# io-headers.net
KiCad netlist of a schematic drawn in Altium Designer
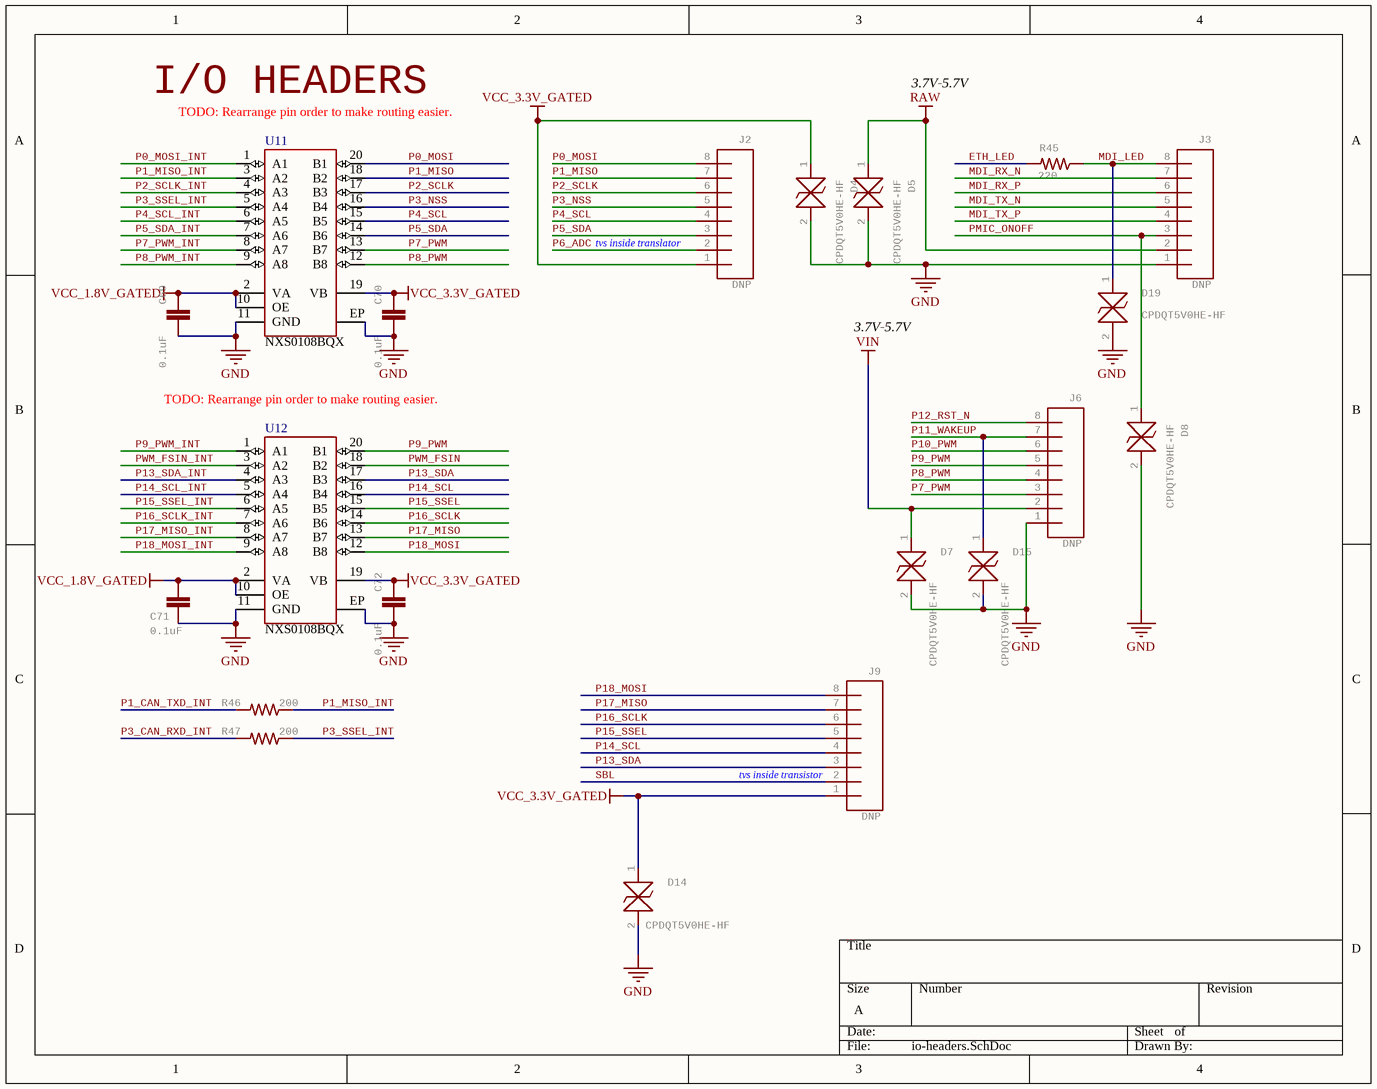
[diagram p0: io-headers.SchDoc]

(export (version "E")
  (design (tool "Eeschema 10.0.6"))
  (components
    (comp (ref "C69")
      (value "0.1uF")
      (footprint "0402-CAP")
      (description "CAPACITOR, European symbol")
      (fields (field (name "MPN") "C0402C104Z4VAC"))
      (libsource (lib "openmv-ae3") (part "C-EUC0201"))
    )
    (comp (ref "C70")
      (value "0.1uF")
      (footprint "0402-CAP")
      (description "CAPACITOR, European symbol")
      (fields (field (name "MPN") "C0402C104Z4VAC"))
      (libsource (lib "openmv-ae3") (part "C-EUC0201"))
    )
    (comp (ref "C71")
      (value "0.1uF")
      (footprint "0402-CAP")
      (description "CAPACITOR, European symbol")
      (fields (field (name "MPN") "C0402C104Z4VAC"))
      (libsource (lib "openmv-ae3") (part "C-EUC0201"))
    )
    (comp (ref "C72")
      (value "0.1uF")
      (footprint "0402-CAP")
      (description "CAPACITOR, European symbol")
      (fields (field (name "MPN") "C0402C104Z4VAC"))
      (libsource (lib "openmv-ae3") (part "C-EUC0201"))
    )
    (comp (ref "D4")
      (value "CPDQT5V0HE-HF")
      (footprint "CPDQT5V0HEHF")
      (description "ESD Suppressors / TVS Diodes DIODE ESD 5VWM 65W 0402/SOD-923F   Source:  Datasheet")
      (fields (field (name "MOUSER_PART_NUMBER") "MOUSER_PART_NUMBER"))
      (libsource (lib "openmv-ae3") (part "CPDQT5V0HE-HF"))
    )
    (comp (ref "D5")
      (value "CPDQT5V0HE-HF")
      (footprint "CPDQT5V0HEHF")
      (description "ESD Suppressors / TVS Diodes DIODE ESD 5VWM 65W 0402/SOD-923F   Source:  Datasheet")
      (fields (field (name "MOUSER_PART_NUMBER") "MOUSER_PART_NUMBER"))
      (libsource (lib "openmv-ae3") (part "CPDQT5V0HE-HF"))
    )
    (comp (ref "D7")
      (value "CPDQT5V0HE-HF")
      (footprint "CPDQT5V0HEHF")
      (description "ESD Suppressors / TVS Diodes DIODE ESD 5VWM 65W 0402/SOD-923F   Source:  Datasheet")
      (fields (field (name "MOUSER_PART_NUMBER") "MOUSER_PART_NUMBER"))
      (libsource (lib "openmv-ae3") (part "CPDQT5V0HE-HF"))
    )
    (comp (ref "D8")
      (value "CPDQT5V0HE-HF")
      (footprint "CPDQT5V0HEHF")
      (description "ESD Suppressors / TVS Diodes DIODE ESD 5VWM 65W 0402/SOD-923F   Source:  Datasheet")
      (fields (field (name "MOUSER_PART_NUMBER") "MOUSER_PART_NUMBER"))
      (libsource (lib "openmv-ae3") (part "CPDQT5V0HE-HF"))
    )
    (comp (ref "D14")
      (value "CPDQT5V0HE-HF")
      (footprint "CPDQT5V0HEHF")
      (description "ESD Suppressors / TVS Diodes DIODE ESD 5VWM 65W 0402/SOD-923F   Source:  Datasheet")
      (fields (field (name "MOUSER_PART_NUMBER") "MOUSER_PART_NUMBER"))
      (libsource (lib "openmv-ae3") (part "CPDQT5V0HE-HF"))
    )
    (comp (ref "D15")
      (value "CPDQT5V0HE-HF")
      (footprint "CPDQT5V0HEHF")
      (description "ESD Suppressors / TVS Diodes DIODE ESD 5VWM 65W 0402/SOD-923F   Source:  Datasheet")
      (fields (field (name "MOUSER_PART_NUMBER") "MOUSER_PART_NUMBER"))
      (libsource (lib "openmv-ae3") (part "CPDQT5V0HE-HF"))
    )
    (comp (ref "D19")
      (value "CPDQT5V0HE-HF")
      (footprint "CPDQT5V0HEHF")
      (description "ESD Suppressors / TVS Diodes DIODE ESD 5VWM 65W 0402/SOD-923F   Source:  Datasheet")
      (fields (field (name "MOUSER_PART_NUMBER") "MOUSER_PART_NUMBER"))
      (libsource (lib "openmv-ae3") (part "CPDQT5V0HE-HF"))
    )
    (comp (ref "J2")
      (value "DNP")
      (footprint "1X08")
      (libsource (lib "openmv-ae3") (part "CONN_08{dblquote}"))
    )
    (comp (ref "J3")
      (value "DNP")
      (footprint "1X08")
      (libsource (lib "openmv-ae3") (part "CONN_08{dblquote}"))
    )
    (comp (ref "J6")
      (value "DNP")
      (footprint "1X08")
      (libsource (lib "openmv-ae3") (part "CONN_08{dblquote}"))
    )
    (comp (ref "J9")
      (value "DNP")
      (footprint "1X08")
      (libsource (lib "openmv-ae3") (part "CONN_08{dblquote}"))
    )
    (comp (ref "R45")
      (value "220")
      (footprint "0402-RES")
      (description "ResistorBasic schematic elements and footprints for 0603, 1206, and PTH resistors.")
      (fields (field (name "MPN") "CRGCQ0402F220R") (field (name "LIBRARYNAME") "sfe"))
      (libsource (lib "openmv-ae3") (part "RESISTOR0402-RES"))
    )
    (comp (ref "R46")
      (value "200")
      (footprint "0402-RES")
      (description "ResistorBasic schematic elements and footprints for 0603, 1206, and PTH resistors.")
      (fields (field (name "MPN") "AC0402JR-07200RL") (field (name "LIBRARYNAME") "sfe"))
      (libsource (lib "openmv-ae3") (part "RESISTOR0402-RES"))
    )
    (comp (ref "R47")
      (value "200")
      (footprint "0402-RES")
      (description "ResistorBasic schematic elements and footprints for 0603, 1206, and PTH resistors.")
      (fields (field (name "MPN") "AC0402JR-07200RL") (field (name "LIBRARYNAME") "sfe"))
      (libsource (lib "openmv-ae3") (part "RESISTOR0402-RES"))
    )
    (comp (ref "U11")
      (value "NXS0108BQX")
      (footprint "DHVQFN20_SOT764-1_NEX")
      (description "No Description Available")
      (fields (field (name "MF") "Nexperia") (field (name "MPN") "NXS0108BQX"))
      (libsource (lib "openmv-ae3") (part "NXS0108BQX"))
    )
    (comp (ref "U12")
      (value "NXS0108BQX")
      (footprint "DHVQFN20_SOT764-1_NEX")
      (description "No Description Available")
      (fields (field (name "MF") "Nexperia") (field (name "MPN") "NXS0108BQX"))
      (libsource (lib "openmv-ae3") (part "NXS0108BQX"))
    )
  )
  (nets
    (net (code "1") (name "/ETH_LED") (class "Default")
      (node (ref "R45") (pin "2") (pinfunction "2_2") (pintype "passive"))
    )
    (net (code "2") (name "/MDI_LED") (class "Default")
      (node (ref "D19") (pin "1") (pinfunction "1_1") (pintype "bidirectional"))
      (node (ref "J3") (pin "8") (pinfunction "8_8") (pintype "passive"))
      (node (ref "R45") (pin "1") (pinfunction "1_1") (pintype "passive"))
    )
    (net (code "3") (name "/MDI_RX_N") (class "Default")
      (node (ref "J3") (pin "7") (pinfunction "7_7") (pintype "passive"))
    )
    (net (code "4") (name "/MDI_RX_P") (class "Default")
      (node (ref "J3") (pin "6") (pinfunction "6_6") (pintype "passive"))
    )
    (net (code "5") (name "/MDI_TX_N") (class "Default")
      (node (ref "J3") (pin "5") (pinfunction "5_5") (pintype "passive"))
    )
    (net (code "6") (name "/MDI_TX_P") (class "Default")
      (node (ref "J3") (pin "4") (pinfunction "4_4") (pintype "passive"))
    )
    (net (code "7") (name "/P0_MOSI") (class "Default")
      (node (ref "J2") (pin "8") (pinfunction "8_8") (pintype "passive"))
      (node (ref "U11") (pin "20") (pinfunction "B1_20") (pintype "bidirectional"))
    )
    (net (code "8") (name "/P0_MOSI_INT") (class "Default")
      (node (ref "U11") (pin "1") (pinfunction "A1_1") (pintype "bidirectional"))
    )
    (net (code "9") (name "/P1_CAN_TXD_INT") (class "Default")
      (node (ref "R46") (pin "2") (pinfunction "2_2") (pintype "passive"))
    )
    (net (code "10") (name "/P1_MISO") (class "Default")
      (node (ref "J2") (pin "7") (pinfunction "7_7") (pintype "passive"))
      (node (ref "U11") (pin "18") (pinfunction "B2_18") (pintype "bidirectional"))
    )
    (net (code "11") (name "/P1_MISO_INT") (class "Default")
      (node (ref "R46") (pin "1") (pinfunction "1_1") (pintype "passive"))
      (node (ref "U11") (pin "3") (pinfunction "A2_3") (pintype "bidirectional"))
    )
    (net (code "12") (name "/P2_SCLK") (class "Default")
      (node (ref "J2") (pin "6") (pinfunction "6_6") (pintype "passive"))
      (node (ref "U11") (pin "17") (pinfunction "B3_17") (pintype "bidirectional"))
    )
    (net (code "13") (name "/P2_SCLK_INT") (class "Default")
      (node (ref "U11") (pin "4") (pinfunction "A3_4") (pintype "bidirectional"))
    )
    (net (code "14") (name "/P3_CAN_RXD_INT") (class "Default")
      (node (ref "R47") (pin "2") (pinfunction "2_2") (pintype "passive"))
    )
    (net (code "15") (name "/P3_NSS") (class "Default")
      (node (ref "J2") (pin "5") (pinfunction "5_5") (pintype "passive"))
      (node (ref "U11") (pin "16") (pinfunction "B4_16") (pintype "bidirectional"))
    )
    (net (code "16") (name "/P3_SSEL_INT") (class "Default")
      (node (ref "R47") (pin "1") (pinfunction "1_1") (pintype "passive"))
      (node (ref "U11") (pin "5") (pinfunction "A4_5") (pintype "bidirectional"))
    )
    (net (code "17") (name "/P4_SCL") (class "Default")
      (node (ref "J2") (pin "4") (pinfunction "4_4") (pintype "passive"))
      (node (ref "U11") (pin "15") (pinfunction "B5_15") (pintype "bidirectional"))
    )
    (net (code "18") (name "/P4_SCL_INT") (class "Default")
      (node (ref "U11") (pin "6") (pinfunction "A5_6") (pintype "bidirectional"))
    )
    (net (code "19") (name "/P5_SDA") (class "Default")
      (node (ref "J2") (pin "3") (pinfunction "3_3") (pintype "passive"))
      (node (ref "U11") (pin "14") (pinfunction "B6_14") (pintype "bidirectional"))
    )
    (net (code "20") (name "/P5_SDA_INT") (class "Default")
      (node (ref "U11") (pin "7") (pinfunction "A6_7") (pintype "bidirectional"))
    )
    (net (code "21") (name "/P6_ADC") (class "Default")
      (node (ref "J2") (pin "2") (pinfunction "2_2") (pintype "passive"))
    )
    (net (code "22") (name "/P7_PWM") (class "Default")
      (node (ref "J6") (pin "3") (pinfunction "3_3") (pintype "passive"))
      (node (ref "U11") (pin "13") (pinfunction "B7_13") (pintype "bidirectional"))
    )
    (net (code "23") (name "/P7_PWM_INT") (class "Default")
      (node (ref "U11") (pin "8") (pinfunction "A7_8") (pintype "bidirectional"))
    )
    (net (code "24") (name "/P8_PWM") (class "Default")
      (node (ref "J6") (pin "4") (pinfunction "4_4") (pintype "passive"))
      (node (ref "U11") (pin "12") (pinfunction "B8_12") (pintype "bidirectional"))
    )
    (net (code "25") (name "/P8_PWM_INT") (class "Default")
      (node (ref "U11") (pin "9") (pinfunction "A8_9") (pintype "bidirectional"))
    )
    (net (code "26") (name "/P9_PWM") (class "Default")
      (node (ref "J6") (pin "5") (pinfunction "5_5") (pintype "passive"))
      (node (ref "U12") (pin "20") (pinfunction "B1_20") (pintype "bidirectional"))
    )
    (net (code "27") (name "/P9_PWM_INT") (class "Default")
      (node (ref "U12") (pin "1") (pinfunction "A1_1") (pintype "bidirectional"))
    )
    (net (code "28") (name "/P10_PWM") (class "Default")
      (node (ref "J6") (pin "6") (pinfunction "6_6") (pintype "passive"))
    )
    (net (code "29") (name "/P11_WAKEUP") (class "Default")
      (node (ref "D15") (pin "1") (pinfunction "1_1") (pintype "bidirectional"))
      (node (ref "J6") (pin "7") (pinfunction "7_7") (pintype "passive"))
    )
    (net (code "30") (name "/P12_RST_N") (class "Default")
      (node (ref "J6") (pin "8") (pinfunction "8_8") (pintype "passive"))
    )
    (net (code "31") (name "/P13_SDA") (class "Default")
      (node (ref "J9") (pin "3") (pinfunction "3_3") (pintype "passive"))
      (node (ref "U12") (pin "17") (pinfunction "B3_17") (pintype "bidirectional"))
    )
    (net (code "32") (name "/P13_SDA_INT") (class "Default")
      (node (ref "U12") (pin "4") (pinfunction "A3_4") (pintype "bidirectional"))
    )
    (net (code "33") (name "/P14_SCL") (class "Default")
      (node (ref "J9") (pin "4") (pinfunction "4_4") (pintype "passive"))
      (node (ref "U12") (pin "16") (pinfunction "B4_16") (pintype "bidirectional"))
    )
    (net (code "34") (name "/P14_SCL_INT") (class "Default")
      (node (ref "U12") (pin "5") (pinfunction "A4_5") (pintype "bidirectional"))
    )
    (net (code "35") (name "/P15_SSEL") (class "Default")
      (node (ref "J9") (pin "5") (pinfunction "5_5") (pintype "passive"))
      (node (ref "U12") (pin "15") (pinfunction "B5_15") (pintype "bidirectional"))
    )
    (net (code "36") (name "/P15_SSEL_INT") (class "Default")
      (node (ref "U12") (pin "6") (pinfunction "A5_6") (pintype "bidirectional"))
    )
    (net (code "37") (name "/P16_SCLK") (class "Default")
      (node (ref "J9") (pin "6") (pinfunction "6_6") (pintype "passive"))
      (node (ref "U12") (pin "14") (pinfunction "B6_14") (pintype "bidirectional"))
    )
    (net (code "38") (name "/P16_SCLK_INT") (class "Default")
      (node (ref "U12") (pin "7") (pinfunction "A6_7") (pintype "bidirectional"))
    )
    (net (code "39") (name "/P17_MISO") (class "Default")
      (node (ref "J9") (pin "7") (pinfunction "7_7") (pintype "passive"))
      (node (ref "U12") (pin "13") (pinfunction "B7_13") (pintype "bidirectional"))
    )
    (net (code "40") (name "/P17_MISO_INT") (class "Default")
      (node (ref "U12") (pin "8") (pinfunction "A7_8") (pintype "bidirectional"))
    )
    (net (code "41") (name "/P18_MOSI") (class "Default")
      (node (ref "J9") (pin "8") (pinfunction "8_8") (pintype "passive"))
      (node (ref "U12") (pin "12") (pinfunction "B8_12") (pintype "bidirectional"))
    )
    (net (code "42") (name "/P18_MOSI_INT") (class "Default")
      (node (ref "U12") (pin "9") (pinfunction "A8_9") (pintype "bidirectional"))
    )
    (net (code "43") (name "/PMIC_ONOFF") (class "Default")
      (node (ref "D8") (pin "1") (pinfunction "1_1") (pintype "bidirectional"))
      (node (ref "J3") (pin "3") (pinfunction "3_3") (pintype "passive"))
    )
    (net (code "44") (name "/PWM_FSIN") (class "Default")
      (node (ref "U12") (pin "18") (pinfunction "B2_18") (pintype "bidirectional"))
    )
    (net (code "45") (name "/PWM_FSIN_INT") (class "Default")
      (node (ref "U12") (pin "3") (pinfunction "A2_3") (pintype "bidirectional"))
    )
    (net (code "46") (name "/SBL") (class "Default")
      (node (ref "J9") (pin "2") (pinfunction "2_2") (pintype "passive"))
    )
    (net (code "47") (name "GND") (class "Default")
      (node (ref "C69") (pin "2") (pinfunction "2_2") (pintype "passive"))
      (node (ref "C70") (pin "2") (pinfunction "2_2") (pintype "passive"))
      (node (ref "C71") (pin "2") (pinfunction "2_2") (pintype "passive"))
      (node (ref "C72") (pin "2") (pinfunction "2_2") (pintype "passive"))
      (node (ref "D14") (pin "2") (pinfunction "2_2") (pintype "bidirectional"))
      (node (ref "D15") (pin "2") (pinfunction "2_2") (pintype "bidirectional"))
      (node (ref "D19") (pin "2") (pinfunction "2_2") (pintype "bidirectional"))
      (node (ref "D4") (pin "2") (pinfunction "2_2") (pintype "bidirectional"))
      (node (ref "D5") (pin "2") (pinfunction "2_2") (pintype "bidirectional"))
      (node (ref "D7") (pin "2") (pinfunction "2_2") (pintype "bidirectional"))
      (node (ref "D8") (pin "2") (pinfunction "2_2") (pintype "bidirectional"))
      (node (ref "J3") (pin "1") (pinfunction "1_1") (pintype "passive"))
      (node (ref "J6") (pin "1") (pinfunction "1_1") (pintype "passive"))
      (node (ref "U11") (pin "11") (pinfunction "GND_11") (pintype "power_in"))
      (node (ref "U11") (pin "EP") (pinfunction "EPAD_EP") (pintype "passive"))
      (node (ref "U12") (pin "11") (pinfunction "GND_11") (pintype "power_in"))
      (node (ref "U12") (pin "EP") (pinfunction "EPAD_EP") (pintype "passive"))
    )
    (net (code "48") (name "RAW") (class "Default")
      (node (ref "D5") (pin "1") (pinfunction "1_1") (pintype "bidirectional"))
      (node (ref "J3") (pin "2") (pinfunction "2_2") (pintype "passive"))
    )
    (net (code "49") (name "VCC_1.8V_GATED") (class "Default")
      (node (ref "C69") (pin "1") (pinfunction "1_1") (pintype "passive"))
      (node (ref "C71") (pin "1") (pinfunction "1_1") (pintype "passive"))
      (node (ref "U11") (pin "10") (pinfunction "OE_10") (pintype "passive"))
      (node (ref "U11") (pin "2") (pinfunction "VA_2") (pintype "power_in"))
      (node (ref "U12") (pin "10") (pinfunction "OE_10") (pintype "passive"))
      (node (ref "U12") (pin "2") (pinfunction "VA_2") (pintype "power_in"))
    )
    (net (code "50") (name "VCC_3.3V_GATED") (class "Default")
      (node (ref "C70") (pin "1") (pinfunction "1_1") (pintype "passive"))
      (node (ref "C72") (pin "1") (pinfunction "1_1") (pintype "passive"))
      (node (ref "D14") (pin "1") (pinfunction "1_1") (pintype "bidirectional"))
      (node (ref "D4") (pin "1") (pinfunction "1_1") (pintype "bidirectional"))
      (node (ref "J2") (pin "1") (pinfunction "1_1") (pintype "passive"))
      (node (ref "J9") (pin "1") (pinfunction "1_1") (pintype "passive"))
      (node (ref "U11") (pin "19") (pinfunction "VB_19") (pintype "power_in"))
      (node (ref "U12") (pin "19") (pinfunction "VB_19") (pintype "power_in"))
    )
    (net (code "51") (name "VIN") (class "Default")
      (node (ref "D7") (pin "1") (pinfunction "1_1") (pintype "bidirectional"))
      (node (ref "J6") (pin "2") (pinfunction "2_2") (pintype "passive"))
    )
  )
)
